# AT89xx_Programmer.net
KiCad netlist of a schematic drawn in Altium Designer
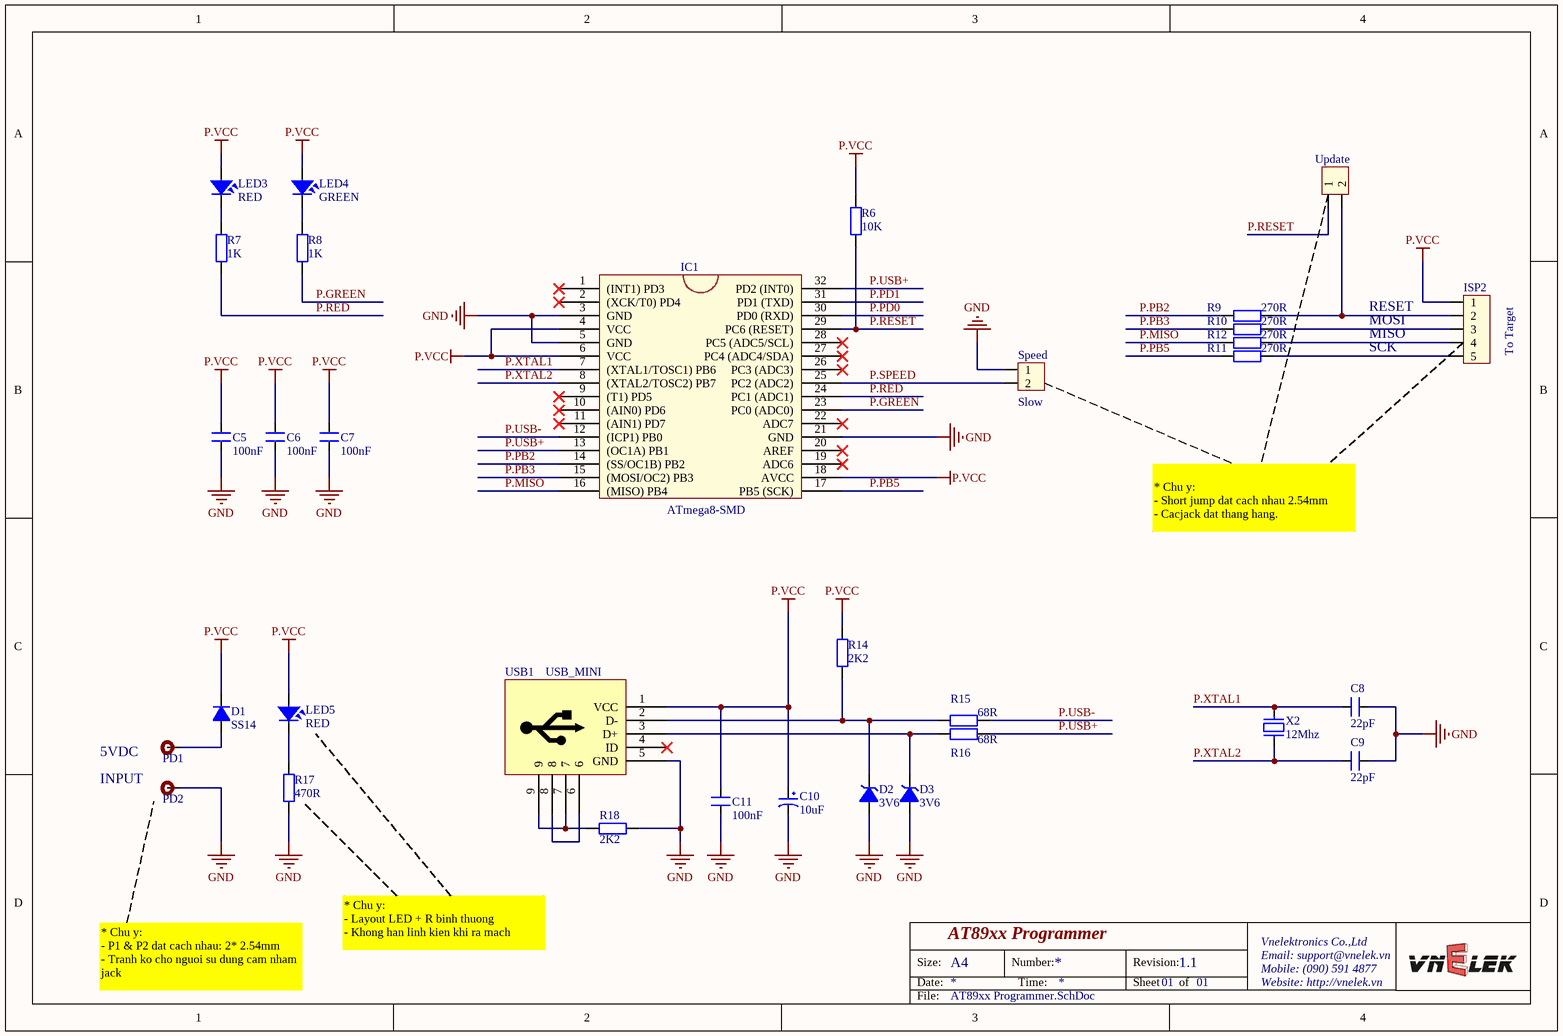
[diagram p0: AT89xx Programmer.SchDoc]

(export (version "E")
  (design (tool "Eeschema 10.0.6"))
  (components
    (comp (ref "C5")
      (value "100nF")
      (footprint "C0805")
      (description "Cap np 104 => 105pF")
      (libsource (lib "syhaunguyen") (part "CN2"))
    )
    (comp (ref "C6")
      (value "100nF")
      (footprint "C0805")
      (description "Cap np 104 => 105pF")
      (libsource (lib "syhaunguyen") (part "CN2"))
    )
    (comp (ref "C7")
      (value "100nF")
      (footprint "C0805")
      (description "Cap np 104 => 105pF")
      (libsource (lib "syhaunguyen") (part "CN2"))
    )
    (comp (ref "C8")
      (value "22pF")
      (footprint "C0603")
      (description "Cap np  1pF - 472pF")
      (libsource (lib "syhaunguyen") (part "CN1"))
    )
    (comp (ref "C9")
      (value "22pF")
      (footprint "C0603")
      (description "Cap np  1pF - 472pF")
      (libsource (lib "syhaunguyen") (part "CN1"))
    )
    (comp (ref "C10")
      (value "10uF")
      (footprint "C1210")
      (description "Cap P  0,1uF < 22uF , 16 - 50V")
      (libsource (lib "syhaunguyen") (part "CP1"))
    )
    (comp (ref "C11")
      (value "100nF")
      (footprint "C0805")
      (description "Cap np 104 => 105pF")
      (libsource (lib "syhaunguyen") (part "CN2"))
    )
    (comp (ref "D1")
      (value "SS14")
      (footprint "SS14")
      (description "Diode 1A")
      (libsource (lib "syhaunguyen") (part "D1A"))
    )
    (comp (ref "D2")
      (value "3V6")
      (footprint "1N5223")
      (description "Diode Zenner")
      (libsource (lib "syhaunguyen") (part "DZ"))
    )
    (comp (ref "D3")
      (value "3V6")
      (footprint "1N5223")
      (description "Diode Zenner")
      (libsource (lib "syhaunguyen") (part "DZ"))
    )
    (comp (ref "IC1")
      (value "ATmega8-SMD")
      (footprint "ATMEGA_8_SMD")
      (description "High-performance, Low-power Atmel  ®  AVR  ®   8-bit Microcontroller")
      (libsource (lib "AT8") (part "ATmega8_SMD_32pin"))
    )
    (comp (ref "ISP2")
      (value "To Target")
      (footprint "Header_5")
      (description "Header 5 (Green)")
      (libsource (lib "Tran Tuan") (part "Hed5"))
    )
    (comp (ref "LED3")
      (value "RED")
      (footprint "Led 0805R")
      (description "LED Single colour Green and Red")
      (libsource (lib "syhaunguyen") (part "LED"))
    )
    (comp (ref "LED4")
      (value "GREEN")
      (footprint "Led 0805G")
      (description "LED Single colour Green and Red")
      (libsource (lib "syhaunguyen") (part "LED"))
    )
    (comp (ref "LED5")
      (value "RED")
      (footprint "Led 0805R")
      (description "LED Single colour Green and Red")
      (libsource (lib "syhaunguyen") (part "LED"))
    )
    (comp (ref "PD1") (value "Pad Big") (libsource (lib "Tran Tuan") (part "Pad_Big")))
    (comp (ref "PD2") (value "Pad Big") (libsource (lib "Tran Tuan") (part "Pad_Big")))
    (comp (ref "R6")
      (value "10K")
      (footprint "RESC2012(0805)")
      (description "Resistor")
      (fields (field (name "Comment") "Res2") (field (name "PUBLISHER") "Altium Limited"))
      (libsource (lib "") (part "Res2_3"))
    )
    (comp (ref "R7")
      (value "1K")
      (footprint "RESC2012(0805)")
      (description "Resistor")
      (fields (field (name "Comment") "Res2") (field (name "PUBLISHER") "Altium Limited"))
      (libsource (lib "Miscellaneous Devices") (part "Res2"))
    )
    (comp (ref "R8")
      (value "1K")
      (footprint "RESC2012(0805)")
      (description "Resistor")
      (fields (field (name "Comment") "Res2") (field (name "PUBLISHER") "Altium Limited"))
      (libsource (lib "Miscellaneous Devices") (part "Res2"))
    )
    (comp (ref "R9")
      (value "270R")
      (footprint "RESC2012(0805)")
      (description "Resistor")
      (fields (field (name "Comment") "Res2") (field (name "PUBLISHER") "Altium Limited"))
      (libsource (lib "") (part "Res2_1"))
    )
    (comp (ref "R10")
      (value "270R")
      (footprint "RESC2012(0805)")
      (description "Resistor")
      (fields (field (name "Comment") "Res2") (field (name "PUBLISHER") "Altium Limited"))
      (libsource (lib "") (part "Res2_1"))
    )
    (comp (ref "R11")
      (value "270R")
      (footprint "RESC2012(0805)")
      (description "Resistor")
      (fields (field (name "Comment") "Res2") (field (name "PUBLISHER") "Altium Limited"))
      (libsource (lib "") (part "Res2_1"))
    )
    (comp (ref "R12")
      (value "270R")
      (footprint "RESC2012(0805)")
      (description "Resistor")
      (fields (field (name "Comment") "Res2") (field (name "PUBLISHER") "Altium Limited"))
      (libsource (lib "") (part "Res2_1"))
    )
    (comp (ref "R14")
      (value "2K2")
      (footprint "RESC2012(0805)")
      (description "Resistor")
      (fields (field (name "Comment") "Res2") (field (name "PUBLISHER") "Altium Limited"))
      (libsource (lib "Miscellaneous Devices") (part "Res2"))
    )
    (comp (ref "R15")
      (value "68R")
      (footprint "RESC2012(0805)")
      (description "Resistor")
      (fields (field (name "Comment") "Res2") (field (name "PUBLISHER") "Altium Limited"))
      (libsource (lib "") (part "Res2_2"))
    )
    (comp (ref "R16")
      (value "68R")
      (footprint "RESC2012(0805)")
      (description "Resistor")
      (fields (field (name "Comment") "Res2") (field (name "PUBLISHER") "Altium Limited"))
      (libsource (lib "") (part "Res2_2"))
    )
    (comp (ref "R17")
      (value "470R")
      (footprint "RESC2012(0805)")
      (description "Resistor")
      (fields (field (name "Comment") "Res2") (field (name "PUBLISHER") "Altium Limited"))
      (libsource (lib "Miscellaneous Devices") (part "Res2"))
    )
    (comp (ref "R18")
      (value "2K2")
      (footprint "RESC2012(0805)")
      (description "Resistor")
      (fields (field (name "Comment") "Res2") (field (name "PUBLISHER") "Altium Limited"))
      (libsource (lib "") (part "Res2_1"))
    )
    (comp (ref "Speed")
      (value "Slow")
      (footprint "Header_2")
      (description "Header 2 (Green)")
      (libsource (lib "syhaunguyen") (part "Hed2"))
    )
    (comp (ref "Update")
      (value "Update")
      (footprint "Header_2")
      (description "Header 2 (Green)")
      (libsource (lib "") (part "Hed2_1"))
    )
    (comp (ref "USB1") (value "USB_MINI") (footprint "USBMNIB") (libsource (lib "lpson") (part "USB_MINI")))
    (comp (ref "X2")
      (value "12Mhz")
      (footprint "CRYSTAL")
      (description "Crystal For all Crystal 2pin.")
      (libsource (lib "syhaunguyen") (part "XT2"))
    )
  )
  (nets
    (net (code "1") (name "/P.GREEN") (class "Default")
      (node (ref "IC1") (pin "23") (pinfunction "PC0_(ADC0)_23") (pintype "passive"))
      (node (ref "R8") (pin "2") (pinfunction "2_2") (pintype "passive"))
    )
    (net (code "2") (name "/P.MISO") (class "Default")
      (node (ref "IC1") (pin "16") (pinfunction "(MISO)_PB4_16") (pintype "passive"))
      (node (ref "R12") (pin "1") (pinfunction "1_1") (pintype "passive"))
    )
    (net (code "3") (name "/P.PB2") (class "Default")
      (node (ref "IC1") (pin "14") (pinfunction "(SS/OC1B)_PB2_14") (pintype "passive"))
      (node (ref "R9") (pin "1") (pinfunction "1_1") (pintype "passive"))
    )
    (net (code "4") (name "/P.PB3") (class "Default")
      (node (ref "IC1") (pin "15") (pinfunction "(MOSI/OC2)_PB3_15") (pintype "passive"))
      (node (ref "R10") (pin "1") (pinfunction "1_1") (pintype "passive"))
    )
    (net (code "5") (name "/P.PB5") (class "Default")
      (node (ref "IC1") (pin "17") (pinfunction "PB5_(SCK)_17") (pintype "passive"))
      (node (ref "R11") (pin "1") (pinfunction "1_1") (pintype "passive"))
    )
    (net (code "6") (name "/P.PD0") (class "Default")
      (node (ref "IC1") (pin "30") (pinfunction "PD0_(RXD)_30") (pintype "passive"))
    )
    (net (code "7") (name "/P.PD1") (class "Default")
      (node (ref "IC1") (pin "31") (pinfunction "PD1_(TXD)_31") (pintype "passive"))
    )
    (net (code "8") (name "/P.RED") (class "Default")
      (node (ref "IC1") (pin "24") (pinfunction "PC1_(ADC1)_24") (pintype "passive"))
      (node (ref "R7") (pin "2") (pinfunction "2_2") (pintype "passive"))
    )
    (net (code "9") (name "/P.RESET") (class "Default")
      (node (ref "IC1") (pin "29") (pinfunction "PC6_(RESET)_29") (pintype "passive"))
      (node (ref "R6") (pin "1") (pinfunction "1_1") (pintype "passive"))
      (node (ref "Update") (pin "1") (pinfunction "1_1") (pintype "passive"))
    )
    (net (code "10") (name "/P.SPEED") (class "Default")
      (node (ref "IC1") (pin "25") (pinfunction "PC2_(ADC2)_25") (pintype "passive"))
      (node (ref "Speed") (pin "2") (pinfunction "2_2") (pintype "passive"))
    )
    (net (code "11") (name "/P.USB+") (class "Default")
      (node (ref "IC1") (pin "13") (pinfunction "(OC1A)_PB1_13") (pintype "passive"))
      (node (ref "IC1") (pin "32") (pinfunction "PD2_(INT0)_32") (pintype "passive"))
      (node (ref "R16") (pin "1") (pinfunction "1_1") (pintype "passive"))
    )
    (net (code "12") (name "/P.USB-") (class "Default")
      (node (ref "IC1") (pin "12") (pinfunction "(ICP1)_PB0_12") (pintype "passive"))
      (node (ref "R15") (pin "1") (pinfunction "1_1") (pintype "passive"))
    )
    (net (code "13") (name "/P.XTAL1") (class "Default")
      (node (ref "C8") (pin "2") (pinfunction "2_2") (pintype "passive"))
      (node (ref "IC1") (pin "7") (pinfunction "(XTAL1/TOSC1)_PB6_7") (pintype "passive"))
      (node (ref "X2") (pin "1") (pinfunction "1_1") (pintype "passive"))
    )
    (net (code "14") (name "/P.XTAL2") (class "Default")
      (node (ref "C9") (pin "2") (pinfunction "2_2") (pintype "passive"))
      (node (ref "IC1") (pin "8") (pinfunction "(XTAL2/TOSC2)_PB7_8") (pintype "passive"))
      (node (ref "X2") (pin "2") (pinfunction "2_2") (pintype "passive"))
    )
    (net (code "15") (name "GND") (class "Default")
      (node (ref "C10") (pin "2") (pinfunction "2_2") (pintype "passive"))
      (node (ref "C11") (pin "1") (pinfunction "1_1") (pintype "passive"))
      (node (ref "C5") (pin "1") (pinfunction "1_1") (pintype "passive"))
      (node (ref "C6") (pin "1") (pinfunction "1_1") (pintype "passive"))
      (node (ref "C7") (pin "1") (pinfunction "1_1") (pintype "passive"))
      (node (ref "C8") (pin "1") (pinfunction "1_1") (pintype "passive"))
      (node (ref "C9") (pin "1") (pinfunction "1_1") (pintype "passive"))
      (node (ref "D2") (pin "1") (pinfunction "A_1") (pintype "passive"))
      (node (ref "D3") (pin "1") (pinfunction "A_1") (pintype "passive"))
      (node (ref "IC1") (pin "21") (pinfunction "GND_21") (pintype "passive"))
      (node (ref "IC1") (pin "3") (pinfunction "GND_3") (pintype "passive"))
      (node (ref "IC1") (pin "5") (pinfunction "GND_5") (pintype "passive"))
      (node (ref "PD2") (pin "1") (pinfunction "1_1") (pintype "passive"))
      (node (ref "R17") (pin "2") (pinfunction "2_2") (pintype "passive"))
      (node (ref "R18") (pin "2") (pinfunction "2_2") (pintype "passive"))
      (node (ref "Speed") (pin "1") (pinfunction "1_1") (pintype "passive"))
      (node (ref "USB1") (pin "5") (pinfunction "GND_5") (pintype "passive"))
    )
    (net (code "16") (name "Net-(D1-A)") (class "Default")
      (node (ref "D1") (pin "1") (pinfunction "A_1") (pintype "passive"))
      (node (ref "PD1") (pin "1") (pinfunction "1_1") (pintype "passive"))
    )
    (net (code "17") (name "Net-(D2-K)") (class "Default")
      (node (ref "D2") (pin "2") (pinfunction "K_2") (pintype "passive"))
      (node (ref "R14") (pin "2") (pinfunction "2_2") (pintype "passive"))
      (node (ref "R15") (pin "2") (pinfunction "2_2") (pintype "passive"))
      (node (ref "USB1") (pin "2") (pinfunction "D-_2") (pintype "passive"))
    )
    (net (code "18") (name "Net-(D3-K)") (class "Default")
      (node (ref "D3") (pin "2") (pinfunction "K_2") (pintype "passive"))
      (node (ref "R16") (pin "2") (pinfunction "2_2") (pintype "passive"))
      (node (ref "USB1") (pin "3") (pinfunction "D+_3") (pintype "passive"))
    )
    (net (code "19") (name "Net-(ISP2-Pad2)") (class "Default")
      (node (ref "ISP2") (pin "2") (pinfunction "2_2") (pintype "passive"))
      (node (ref "R9") (pin "2") (pinfunction "2_2") (pintype "passive"))
      (node (ref "Update") (pin "2") (pinfunction "2_2") (pintype "passive"))
    )
    (net (code "20") (name "Net-(ISP2-Pad3)") (class "Default")
      (node (ref "ISP2") (pin "3") (pinfunction "3_3") (pintype "passive"))
      (node (ref "R10") (pin "2") (pinfunction "2_2") (pintype "passive"))
    )
    (net (code "21") (name "Net-(ISP2-Pad4)") (class "Default")
      (node (ref "ISP2") (pin "4") (pinfunction "4_4") (pintype "passive"))
      (node (ref "R12") (pin "2") (pinfunction "2_2") (pintype "passive"))
    )
    (net (code "22") (name "Net-(ISP2-Pad5)") (class "Default")
      (node (ref "ISP2") (pin "5") (pinfunction "5_5") (pintype "passive"))
      (node (ref "R11") (pin "2") (pinfunction "2_2") (pintype "passive"))
    )
    (net (code "23") (name "Net-(LED3-Pad2)") (class "Default")
      (node (ref "LED3") (pin "2") (pinfunction "2_2") (pintype "passive"))
      (node (ref "R7") (pin "1") (pinfunction "1_1") (pintype "passive"))
    )
    (net (code "24") (name "Net-(LED4-Pad2)") (class "Default")
      (node (ref "LED4") (pin "2") (pinfunction "2_2") (pintype "passive"))
      (node (ref "R8") (pin "1") (pinfunction "1_1") (pintype "passive"))
    )
    (net (code "25") (name "Net-(LED5-Pad2)") (class "Default")
      (node (ref "LED5") (pin "2") (pinfunction "2_2") (pintype "passive"))
      (node (ref "R17") (pin "1") (pinfunction "1_1") (pintype "passive"))
    )
    (net (code "26") (name "Net-(R18-Pad1)") (class "Default")
      (node (ref "R18") (pin "1") (pinfunction "1_1") (pintype "passive"))
      (node (ref "USB1") (pin "7") (pinfunction "7_7") (pintype "passive"))
      (node (ref "USB1") (pin "9") (pinfunction "9_9") (pintype "passive"))
    )
    (net (code "27") (name "Net-(USB1-Pad6)") (class "Default")
      (node (ref "USB1") (pin "6") (pinfunction "6_6") (pintype "passive"))
      (node (ref "USB1") (pin "8") (pinfunction "8_8") (pintype "passive"))
    )
    (net (code "28") (name "P.VCC") (class "Default")
      (node (ref "C10") (pin "1") (pinfunction "1_1") (pintype "passive"))
      (node (ref "C11") (pin "2") (pinfunction "2_2") (pintype "passive"))
      (node (ref "C5") (pin "2") (pinfunction "2_2") (pintype "passive"))
      (node (ref "C6") (pin "2") (pinfunction "2_2") (pintype "passive"))
      (node (ref "C7") (pin "2") (pinfunction "2_2") (pintype "passive"))
      (node (ref "D1") (pin "2") (pinfunction "K_2") (pintype "passive"))
      (node (ref "IC1") (pin "18") (pinfunction "AVCC_18") (pintype "passive"))
      (node (ref "IC1") (pin "4") (pinfunction "VCC_4") (pintype "passive"))
      (node (ref "IC1") (pin "6") (pinfunction "VCC_6") (pintype "passive"))
      (node (ref "ISP2") (pin "1") (pinfunction "1_1") (pintype "passive"))
      (node (ref "LED3") (pin "1") (pinfunction "1_1") (pintype "passive"))
      (node (ref "LED4") (pin "1") (pinfunction "1_1") (pintype "passive"))
      (node (ref "LED5") (pin "1") (pinfunction "1_1") (pintype "passive"))
      (node (ref "R14") (pin "1") (pinfunction "1_1") (pintype "passive"))
      (node (ref "R6") (pin "2") (pinfunction "2_2") (pintype "passive"))
      (node (ref "USB1") (pin "1") (pinfunction "VCC_1") (pintype "passive"))
    )
    (net (code "29") (name "unconnected-(IC1-(AIN0)_PD6-Pad10)") (class "Default")
      (node (ref "IC1") (pin "10") (pinfunction "(AIN0)_PD6_10") (pintype "passive+no_connect"))
    )
    (net (code "30") (name "unconnected-(IC1-(AIN1)_PD7-Pad11)") (class "Default")
      (node (ref "IC1") (pin "11") (pinfunction "(AIN1)_PD7_11") (pintype "passive+no_connect"))
    )
    (net (code "31") (name "unconnected-(IC1-(INT1)_PD3-Pad1)") (class "Default")
      (node (ref "IC1") (pin "1") (pinfunction "(INT1)_PD3_1") (pintype "passive+no_connect"))
    )
    (net (code "32") (name "unconnected-(IC1-(T1)_PD5-Pad9)") (class "Default")
      (node (ref "IC1") (pin "9") (pinfunction "(T1)_PD5_9") (pintype "passive+no_connect"))
    )
    (net (code "33") (name "unconnected-(IC1-(XCK{slash}T0)_PD4-Pad2)") (class "Default")
      (node (ref "IC1") (pin "2") (pinfunction "(XCK/T0)_PD4_2") (pintype "passive+no_connect"))
    )
    (net (code "34") (name "unconnected-(IC1-ADC6-Pad19)") (class "Default")
      (node (ref "IC1") (pin "19") (pinfunction "ADC6_19") (pintype "passive+no_connect"))
    )
    (net (code "35") (name "unconnected-(IC1-ADC7-Pad22)") (class "Default")
      (node (ref "IC1") (pin "22") (pinfunction "ADC7_22") (pintype "passive+no_connect"))
    )
    (net (code "36") (name "unconnected-(IC1-AREF-Pad20)") (class "Default")
      (node (ref "IC1") (pin "20") (pinfunction "AREF_20") (pintype "passive+no_connect"))
    )
    (net (code "37") (name "unconnected-(IC1-PC3_(ADC3)-Pad26)") (class "Default")
      (node (ref "IC1") (pin "26") (pinfunction "PC3_(ADC3)_26") (pintype "passive+no_connect"))
    )
    (net (code "38") (name "unconnected-(IC1-PC4_(ADC4{slash}SDA)-Pad27)") (class "Default")
      (node (ref "IC1") (pin "27") (pinfunction "PC4_(ADC4/SDA)_27") (pintype "passive+no_connect"))
    )
    (net (code "39") (name "unconnected-(IC1-PC5_(ADC5{slash}SCL)-Pad28)") (class "Default")
      (node (ref "IC1") (pin "28") (pinfunction "PC5_(ADC5/SCL)_28") (pintype "passive+no_connect"))
    )
    (net (code "40") (name "unconnected-(USB1-ID-Pad4)") (class "Default")
      (node (ref "USB1") (pin "4") (pinfunction "ID_4") (pintype "passive+no_connect"))
    )
  )
)
